# MainMCU.net
KiCad netlist of a schematic drawn in Altium Designer
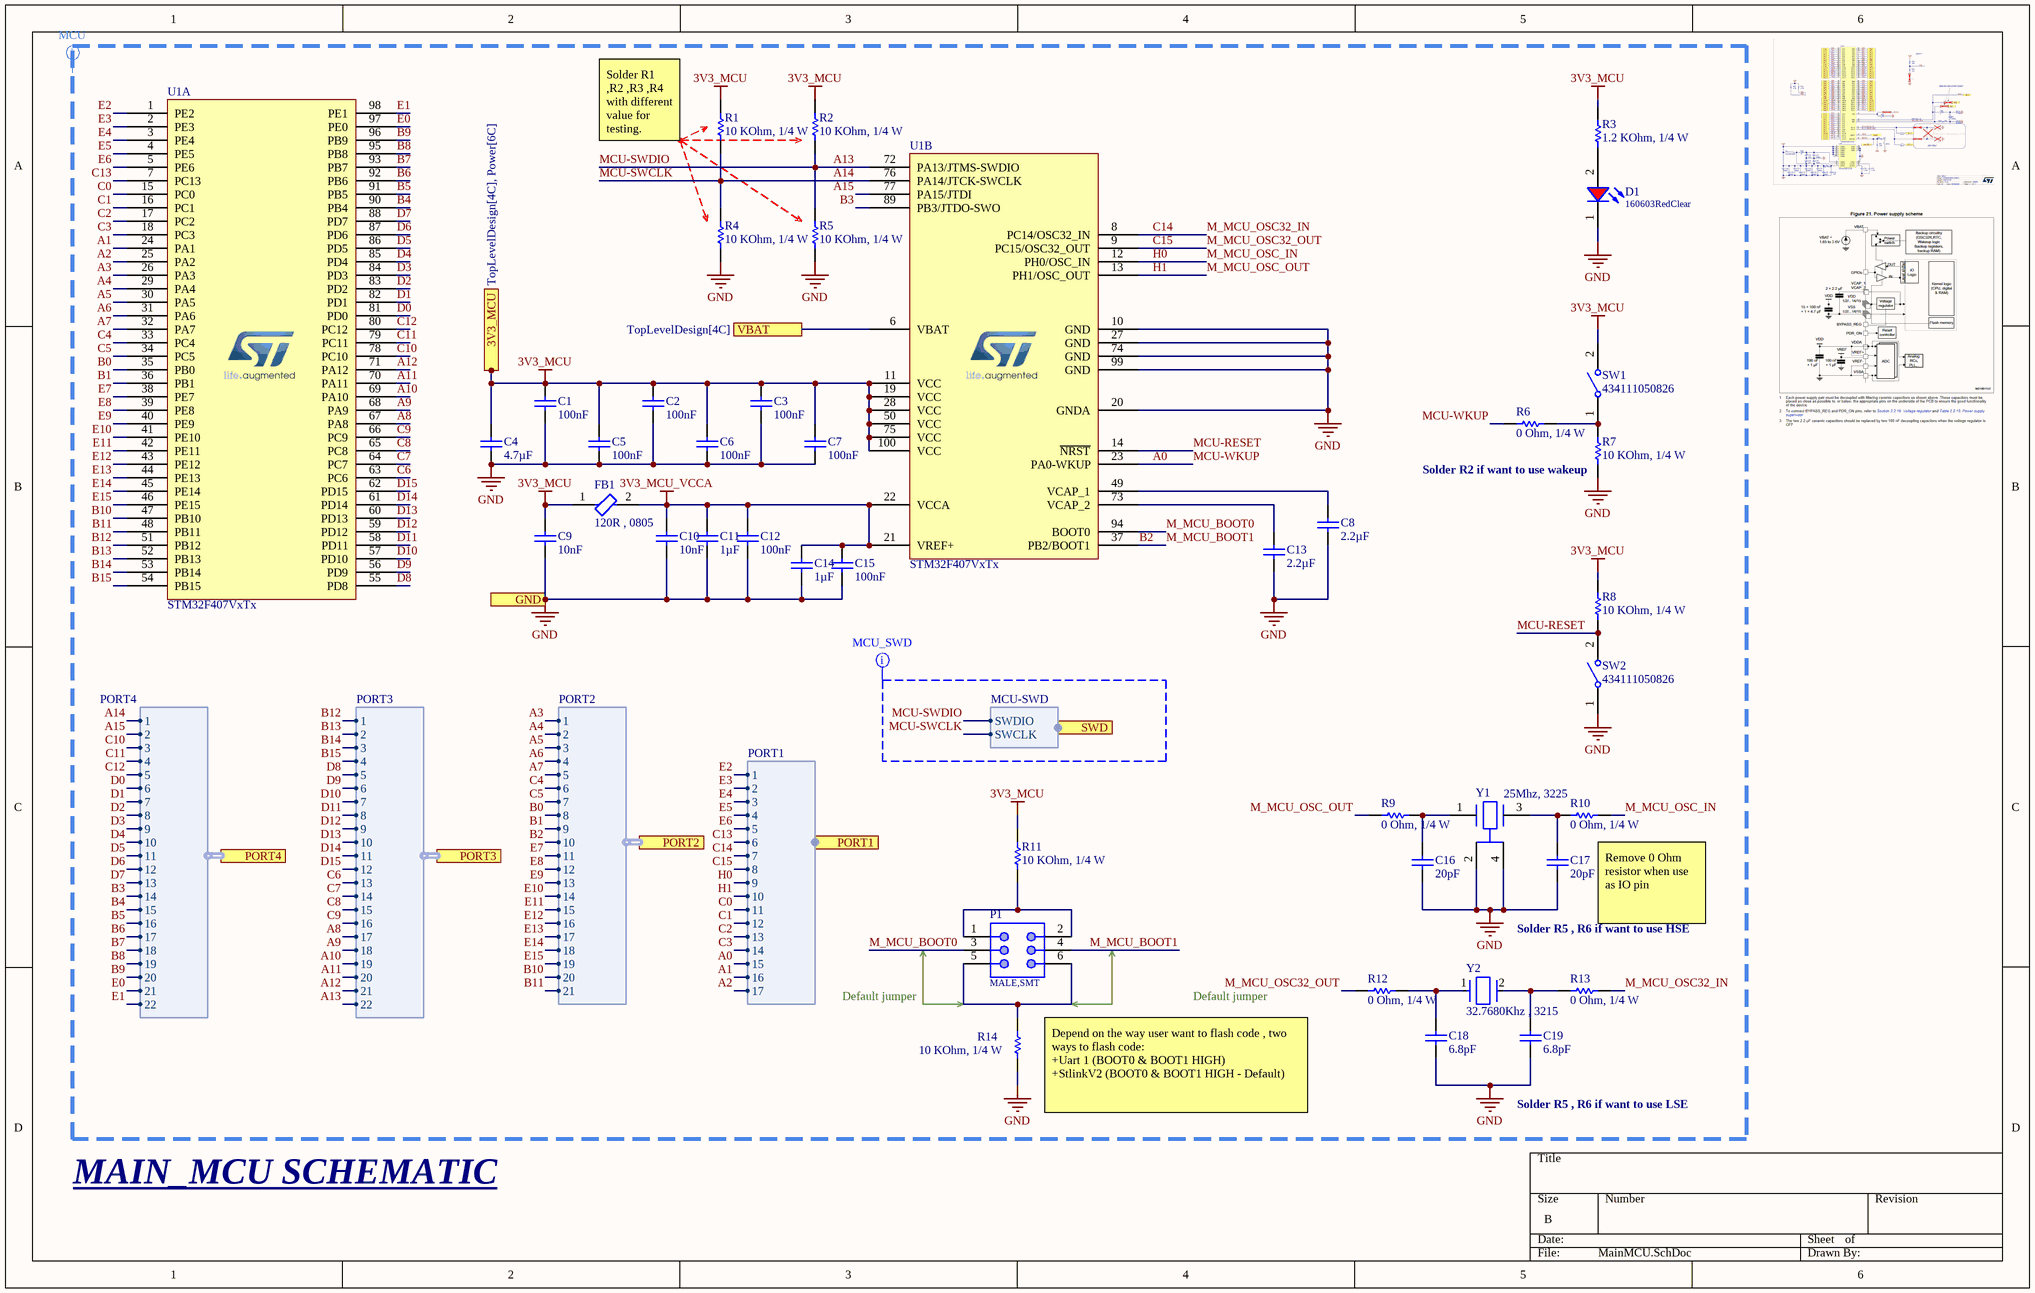
[diagram p0: MainMCU.SchDoc]

(export (version "E")
  (design (tool "Eeschema 10.0.6"))
  (components
    (comp (ref "C1")
      (value "100nF")
      (footprint "CAP_0603")
      (description "CAP, size 0603, 100 nF, 50 VDC")
      (fields
        (field (name "TOLERANCE") "5%")
        (field (name "Comment") "0106031010550")
        (field (name "SOURCE") "Capacitor_0603_5_percent.SchLib")
      )
      (libsource (lib "Tin Tran") (part "0106036820550"))
    )
    (comp (ref "C2")
      (value "100nF")
      (footprint "CAP_0603")
      (description "CAP, size 0603, 100 nF, 50 VDC")
      (fields
        (field (name "TOLERANCE") "5%")
        (field (name "Comment") "0106031010550")
        (field (name "SOURCE") "Capacitor_0603_5_percent.SchLib")
      )
      (libsource (lib "Tin Tran") (part "0106036820550"))
    )
    (comp (ref "C3")
      (value "100nF")
      (footprint "CAP_0603")
      (description "CAP, size 0603, 100 nF, 50 VDC")
      (fields
        (field (name "TOLERANCE") "5%")
        (field (name "Comment") "0106031010550")
        (field (name "SOURCE") "Capacitor_0603_5_percent.SchLib")
      )
      (libsource (lib "Tin Tran") (part "0106036820550"))
    )
    (comp (ref "C4")
      (value "4.7µF")
      (footprint "CAP_0603")
      (description "CAP, size 0603, 4.7 uF, 10 VDC")
      (fields
        (field (name "TOLERANCE") "10%")
        (field (name "Comment") "0106034751010")
        (field (name "SOURCE") "Capacitor_0603_10_percent.SchLib")
      )
      (libsource (lib "Tin Tran") (part "010603475106.3"))
    )
    (comp (ref "C5")
      (value "100nF")
      (footprint "CAP_0603")
      (description "CAP, size 0603, 100 nF, 50 VDC")
      (fields
        (field (name "TOLERANCE") "5%")
        (field (name "Comment") "0106031010550")
        (field (name "SOURCE") "Capacitor_0603_5_percent.SchLib")
      )
      (libsource (lib "Tin Tran") (part "0106036820550"))
    )
    (comp (ref "C6")
      (value "100nF")
      (footprint "CAP_0603")
      (description "CAP, size 0603, 100 nF, 50 VDC")
      (fields
        (field (name "TOLERANCE") "5%")
        (field (name "Comment") "0106031010550")
        (field (name "SOURCE") "Capacitor_0603_5_percent.SchLib")
      )
      (libsource (lib "Tin Tran") (part "0106036820550"))
    )
    (comp (ref "C7")
      (value "100nF")
      (footprint "CAP_0603")
      (description "CAP, size 0603, 100 nF, 50 VDC")
      (fields
        (field (name "TOLERANCE") "5%")
        (field (name "Comment") "0106031010550")
        (field (name "SOURCE") "Capacitor_0603_5_percent.SchLib")
      )
      (libsource (lib "Tin Tran") (part "0106036820550"))
    )
    (comp (ref "C8")
      (value "2.2µF")
      (footprint "CAP_0603")
      (description "CAP, size 0603, 2.2 uF, 10 VDC")
      (fields
        (field (name "TOLERANCE") "10%")
        (field (name "Comment") "0106032251010")
        (field (name "SOURCE") "Capacitor_0603_10_percent.SchLib")
      )
      (libsource (lib "Tin Tran") (part "010603475106.3"))
    )
    (comp (ref "C9")
      (value "10nF")
      (footprint "CAP_0603")
      (description "CAP, size 0603, 10 nF, 50 VDC")
      (fields
        (field (name "TOLERANCE") "5%")
        (field (name "Comment") "0106031030550")
        (field (name "SOURCE") "Capacitor_0603_5_percent.SchLib")
      )
      (libsource (lib "Tin Tran") (part "0106036820550"))
    )
    (comp (ref "C10")
      (value "10nF")
      (footprint "CAP_0603")
      (description "CAP, size 0603, 10 nF, 50 VDC")
      (fields
        (field (name "TOLERANCE") "5%")
        (field (name "Comment") "0106031030550")
        (field (name "SOURCE") "Capacitor_0603_5_percent.SchLib")
      )
      (libsource (lib "Tin Tran") (part "0106036820550"))
    )
    (comp (ref "C11")
      (value "1µF")
      (footprint "CAP_0603")
      (description "CAP, size 0603, 1 uF, 35 VDC")
      (fields
        (field (name "TOLERANCE") "10%")
        (field (name "Comment") "0106031051035")
        (field (name "SOURCE") "Capacitor_0603_10_percent.SchLib")
      )
      (libsource (lib "Tin Tran") (part "010603475106.3"))
    )
    (comp (ref "C12")
      (value "100nF")
      (footprint "CAP_0603")
      (description "CAP, size 0603, 100 nF, 50 VDC")
      (fields
        (field (name "TOLERANCE") "5%")
        (field (name "Comment") "0106031010550")
        (field (name "SOURCE") "Capacitor_0603_5_percent.SchLib")
      )
      (libsource (lib "Tin Tran") (part "0106036820550"))
    )
    (comp (ref "C13")
      (value "2.2µF")
      (footprint "CAP_0603")
      (description "CAP, size 0603, 2.2 uF, 10 VDC")
      (fields
        (field (name "TOLERANCE") "10%")
        (field (name "Comment") "0106032251010")
        (field (name "SOURCE") "Capacitor_0603_10_percent.SchLib")
      )
      (libsource (lib "Tin Tran") (part "010603475106.3"))
    )
    (comp (ref "C14")
      (value "1µF")
      (footprint "CAP_0603")
      (description "CAP, size 0603, 1 uF, 35 VDC")
      (fields
        (field (name "TOLERANCE") "10%")
        (field (name "Comment") "0106031051035")
        (field (name "SOURCE") "Capacitor_0603_10_percent.SchLib")
      )
      (libsource (lib "Tin Tran") (part "010603475106.3"))
    )
    (comp (ref "C15")
      (value "100nF")
      (footprint "CAP_0603")
      (description "CAP, size 0603, 100 nF, 50 VDC")
      (fields
        (field (name "TOLERANCE") "5%")
        (field (name "Comment") "0106031010550")
        (field (name "SOURCE") "Capacitor_0603_5_percent.SchLib")
      )
      (libsource (lib "Tin Tran") (part "0106036820550"))
    )
    (comp (ref "C16")
      (value "20pF")
      (footprint "CAP_0603")
      (description "CAP, size 0603, 20 pF, 50 VDC")
      (fields
        (field (name "TOLERANCE") "5%")
        (field (name "Comment") "0106031000550")
        (field (name "SOURCE") "Capacitor_0603_5_percent.SchLib")
      )
      (libsource (lib "Tin Tran") (part "0106036820550"))
    )
    (comp (ref "C17")
      (value "20pF")
      (footprint "CAP_0603")
      (description "CAP, size 0603, 20 pF, 50 VDC")
      (fields
        (field (name "TOLERANCE") "5%")
        (field (name "Comment") "0106031000550")
        (field (name "SOURCE") "Capacitor_0603_5_percent.SchLib")
      )
      (libsource (lib "Tin Tran") (part "0106036820550"))
    )
    (comp (ref "C18")
      (value "6.8pF")
      (footprint "CAP_0603")
      (description "CAP, size 0603, 6.8 pF, 50 VDC")
      (fields
        (field (name "TOLERANCE") "5%")
        (field (name "Comment") "0106031000550")
        (field (name "SOURCE") "Capacitor_0603_5_percent.SchLib")
      )
      (libsource (lib "Tin Tran") (part "0106036820550"))
    )
    (comp (ref "C19")
      (value "6.8pF")
      (footprint "CAP_0603")
      (description "CAP, size 0603, 6.8 pF, 50 VDC")
      (fields
        (field (name "TOLERANCE") "5%")
        (field (name "Comment") "0106031000550")
        (field (name "SOURCE") "Capacitor_0603_5_percent.SchLib")
      )
      (libsource (lib "Tin Tran") (part "0106036820550"))
    )
    (comp (ref "D1")
      (value "160603RedClear")
      (footprint "WL-SMCW_0603_H=0.7mm")
      (description "WL-SMCW SMT Mono-color Chip LED Waterclear, size 0603, Red, 2V, 140deg")
      (libsource (lib "Tin Tran") (part "160603RedClear"))
    )
    (comp (ref "FB1")
      (value "120R , 0805")
      (footprint "FP-BLM18-0_15-t0_8-MFG")
      (description "Ferrite Chip, 1 Function(s), 2A, 2 Pin(s)")
      (libsource (lib "Tin Tran") (part "5f30dd21d616792df468990f7003faa"))
    )
    (comp (ref "P1")
      (value "MALE,SMT")
      (footprint "61030621121")
      (description "WR-PHD Pin Header, SMT, pitch 2.54mm, Dual Row, Vertical, 6p")
      (fields
        (field (name "MANUFACTURER") "Wurth Elektronik")
        (field (name "MANUFACTURER PART NUMBER") "61030621121")
      )
      (libsource (lib "Tin Tran") (part "61300621121"))
    )
    (comp (ref "R1")
      (value "10 KOhm, 1/4 W")
      (footprint "resistor_0603")
      (description "RES, size 0603, 10 KOhm, 1/4 W")
      (fields (field (name "Comment") "0006031031"))
      (libsource (lib "Tin Tran") (part "00060371541"))
    )
    (comp (ref "R2")
      (value "10 KOhm, 1/4 W")
      (footprint "resistor_0603")
      (description "RES, size 0603, 10 KOhm, 1/4 W")
      (fields (field (name "Comment") "0006031031"))
      (libsource (lib "Tin Tran") (part "00060371541"))
    )
    (comp (ref "R3")
      (value "1.2 KOhm, 1/4 W")
      (footprint "resistor_0603")
      (description "RES, size 0603, 1.2 KOhm, 1/4 W")
      (fields (field (name "Comment") "0006031221"))
      (libsource (lib "Tin Tran") (part "00060371541"))
    )
    (comp (ref "R4")
      (value "10 KOhm, 1/4 W")
      (footprint "resistor_0603")
      (description "RES, size 0603, 10 KOhm, 1/4 W")
      (fields (field (name "Comment") "0006031031"))
      (libsource (lib "Tin Tran") (part "00060371541"))
    )
    (comp (ref "R5")
      (value "10 KOhm, 1/4 W")
      (footprint "resistor_0603")
      (description "RES, size 0603, 10 KOhm, 1/4 W")
      (fields (field (name "Comment") "0006031031"))
      (libsource (lib "Tin Tran") (part "00060371541"))
    )
    (comp (ref "R6")
      (value "0 Ohm, 1/4 W")
      (footprint "resistor_0603")
      (description "RES, size 0603, 0 Ohm, 1/4 W")
      (fields (field (name "Comment") "0006030001"))
      (libsource (lib "Tin Tran") (part "00060371541"))
    )
    (comp (ref "R7")
      (value "10 KOhm, 1/4 W")
      (footprint "resistor_0603")
      (description "RES, size 0603, 10 KOhm, 1/4 W")
      (fields (field (name "Comment") "0006031031"))
      (libsource (lib "Tin Tran") (part "00060371541"))
    )
    (comp (ref "R8")
      (value "10 KOhm, 1/4 W")
      (footprint "resistor_0603")
      (description "RES, size 0603, 10 KOhm, 1/4 W")
      (fields (field (name "Comment") "0006031031"))
      (libsource (lib "Tin Tran") (part "00060371541"))
    )
    (comp (ref "R9")
      (value "0 Ohm, 1/4 W")
      (footprint "resistor_0603")
      (description "RES, size 0603, 0 Ohm, 1/4 W")
      (fields (field (name "Comment") "0006030001"))
      (libsource (lib "Tin Tran") (part "00060371541"))
    )
    (comp (ref "R10")
      (value "0 Ohm, 1/4 W")
      (footprint "resistor_0603")
      (description "RES, size 0603, 0 Ohm, 1/4 W")
      (fields (field (name "Comment") "0006030001"))
      (libsource (lib "Tin Tran") (part "00060371541"))
    )
    (comp (ref "R11")
      (value "10 KOhm, 1/4 W")
      (footprint "resistor_0603")
      (description "RES, size 0603, 10 KOhm, 1/4 W")
      (fields (field (name "Comment") "0006031031"))
      (libsource (lib "Tin Tran") (part "00060371541"))
    )
    (comp (ref "R12")
      (value "0 Ohm, 1/4 W")
      (footprint "resistor_0603")
      (description "RES, size 0603, 0 Ohm, 1/4 W")
      (fields (field (name "Comment") "0006030001"))
      (libsource (lib "Tin Tran") (part "00060371541"))
    )
    (comp (ref "R13")
      (value "0 Ohm, 1/4 W")
      (footprint "resistor_0603")
      (description "RES, size 0603, 0 Ohm, 1/4 W")
      (fields (field (name "Comment") "0006030001"))
      (libsource (lib "Tin Tran") (part "00060371541"))
    )
    (comp (ref "R14")
      (value "10 KOhm, 1/4 W")
      (footprint "resistor_0603")
      (description "RES, size 0603, 10 KOhm, 1/4 W")
      (fields (field (name "Comment") "0006031031"))
      (libsource (lib "Tin Tran") (part "00060371541"))
    )
    (comp (ref "SW1")
      (value "434111050826")
      (footprint "WS-TASV_L6W3.5H5_4341x10508x6")
      (description "WS-TASV SMT Tact Switch, L6 x W3.5 x H5mm, 260g, SPST-NO, 12V, 50mA")
      (fields (field (name "MANUFACTURER") "Wurth Elektronik"))
      (libsource (lib "Tin Tran") (part "434111050826"))
    )
    (comp (ref "SW2")
      (value "434111050826")
      (footprint "WS-TASV_L6W3.5H5_4341x10508x6")
      (description "WS-TASV SMT Tact Switch, L6 x W3.5 x H5mm, 260g, SPST-NO, 12V, 50mA")
      (fields (field (name "MANUFACTURER") "Wurth Elektronik"))
      (libsource (lib "Tin Tran") (part "434111050826"))
    )
    (comp (ref "U1")
      (value "STM32F407VxTx")
      (footprint "STM32F407VGTx")
      (description "ARM Microcontrollers - MCU ARM M4 1024 FLASH 168 Mhz 192kB SRAM")
      (fields (field (name "PART NUMBER") "STM32F407IGTx") (field (name "MANUFACTURER") "STM"))
      (libsource (lib "Tin Tran") (part "STM32F407VGTx"))
    )
    (comp (ref "Y1")
      (value "25Mhz, 3225")
      (footprint "FP-NX3225SA-MFG")
      (description "CRYSTAL 25.0000MHZ 8PF SMD")
      (fields
        (field (name "OCTOPART") "https://octopart.com/nx3225sa-25.000m-std-crs-2-ndk-51374293")
        (field (name "TOLERANCE") "15ppm")
      )
      (libsource (lib "Tin Tran") (part "CMP-200220-000002-1"))
    )
    (comp (ref "Y2")
      (value "32.7680Khz , 3215")
      (footprint "FP-FC-135-MFG")
      (description "Parallel - Fundamental Quartz Crystal, 0.032768MHz Nom")
      (libsource (lib "Tin Tran") (part "c23a69dc6c9e2f18f2079038eb95dd1"))
    )
  )
  (nets
    (net (code "6") (name "/A0") (class "Default")
      (node (ref "R6") (pin "1") (pinfunction "1_1") (pintype "passive"))
      (node (ref "U1") (pin "23") (pinfunction "PA0-WKUP_23") (pintype "passive"))
    )
    (net (code "7") (name "/A1") (class "Default")
      (node (ref "U1") (pin "24") (pinfunction "PA1_24") (pintype "passive"))
    )
    (net (code "8") (name "/A2") (class "Default")
      (node (ref "U1") (pin "25") (pinfunction "PA2_25") (pintype "passive"))
    )
    (net (code "9") (name "/A3") (class "Default")
      (node (ref "U1") (pin "26") (pinfunction "PA3_26") (pintype "passive"))
    )
    (net (code "10") (name "/A4") (class "Default")
      (node (ref "U1") (pin "29") (pinfunction "PA4_29") (pintype "passive"))
    )
    (net (code "11") (name "/A5") (class "Default")
      (node (ref "U1") (pin "30") (pinfunction "PA5_30") (pintype "passive"))
    )
    (net (code "12") (name "/A6") (class "Default")
      (node (ref "U1") (pin "31") (pinfunction "PA6_31") (pintype "passive"))
    )
    (net (code "13") (name "/A7") (class "Default")
      (node (ref "U1") (pin "32") (pinfunction "PA7_32") (pintype "passive"))
    )
    (net (code "14") (name "/A8") (class "Default")
      (node (ref "U1") (pin "67") (pinfunction "PA8_67") (pintype "passive"))
    )
    (net (code "15") (name "/A9") (class "Default")
      (node (ref "U1") (pin "68") (pinfunction "PA9_68") (pintype "passive"))
    )
    (net (code "16") (name "/A10") (class "Default")
      (node (ref "U1") (pin "69") (pinfunction "PA10_69") (pintype "passive"))
    )
    (net (code "17") (name "/A11") (class "Default")
      (node (ref "U1") (pin "70") (pinfunction "PA11_70") (pintype "passive"))
    )
    (net (code "18") (name "/A12") (class "Default")
      (node (ref "U1") (pin "71") (pinfunction "PA12_71") (pintype "passive"))
    )
    (net (code "19") (name "/A13") (class "Default")
      (node (ref "R2") (pin "1") (pinfunction "1_1") (pintype "passive"))
      (node (ref "R5") (pin "2") (pinfunction "2_2") (pintype "passive"))
      (node (ref "U1") (pin "72") (pinfunction "PA13/JTMS-SWDIO_72") (pintype "passive"))
    )
    (net (code "20") (name "/A14") (class "Default")
      (node (ref "R1") (pin "1") (pinfunction "1_1") (pintype "passive"))
      (node (ref "R4") (pin "2") (pinfunction "2_2") (pintype "passive"))
      (node (ref "U1") (pin "76") (pinfunction "PA14/JTCK-SWCLK_76") (pintype "passive"))
    )
    (net (code "21") (name "/A15") (class "Default")
      (node (ref "U1") (pin "77") (pinfunction "PA15/JTDI_77") (pintype "passive"))
    )
    (net (code "22") (name "/B0") (class "Default")
      (node (ref "U1") (pin "35") (pinfunction "PB0_35") (pintype "passive"))
    )
    (net (code "23") (name "/B1") (class "Default")
      (node (ref "U1") (pin "36") (pinfunction "PB1_36") (pintype "passive"))
    )
    (net (code "24") (name "/B2") (class "Default")
      (node (ref "P1") (pin "4") (pinfunction "4_4") (pintype "passive"))
      (node (ref "U1") (pin "37") (pinfunction "PB2/BOOT1_37") (pintype "passive"))
    )
    (net (code "25") (name "/B3") (class "Default")
      (node (ref "U1") (pin "89") (pinfunction "PB3/JTDO-SWO_89") (pintype "passive"))
    )
    (net (code "26") (name "/B4") (class "Default")
      (node (ref "U1") (pin "90") (pinfunction "PB4_90") (pintype "passive"))
    )
    (net (code "27") (name "/B5") (class "Default")
      (node (ref "U1") (pin "91") (pinfunction "PB5_91") (pintype "passive"))
    )
    (net (code "28") (name "/B6") (class "Default")
      (node (ref "U1") (pin "92") (pinfunction "PB6_92") (pintype "passive"))
    )
    (net (code "29") (name "/B7") (class "Default")
      (node (ref "U1") (pin "93") (pinfunction "PB7_93") (pintype "passive"))
    )
    (net (code "30") (name "/B8") (class "Default")
      (node (ref "U1") (pin "95") (pinfunction "PB8_95") (pintype "passive"))
    )
    (net (code "31") (name "/B9") (class "Default")
      (node (ref "U1") (pin "96") (pinfunction "PB9_96") (pintype "passive"))
    )
    (net (code "32") (name "/B10") (class "Default")
      (node (ref "U1") (pin "47") (pinfunction "PB10_47") (pintype "passive"))
    )
    (net (code "33") (name "/B11") (class "Default")
      (node (ref "U1") (pin "48") (pinfunction "PB11_48") (pintype "passive"))
    )
    (net (code "34") (name "/B12") (class "Default")
      (node (ref "U1") (pin "51") (pinfunction "PB12_51") (pintype "passive"))
    )
    (net (code "35") (name "/B13") (class "Default")
      (node (ref "U1") (pin "52") (pinfunction "PB13_52") (pintype "passive"))
    )
    (net (code "36") (name "/B14") (class "Default")
      (node (ref "U1") (pin "53") (pinfunction "PB14_53") (pintype "passive"))
    )
    (net (code "37") (name "/B15") (class "Default")
      (node (ref "U1") (pin "54") (pinfunction "PB15_54") (pintype "passive"))
    )
    (net (code "38") (name "/C0") (class "Default")
      (node (ref "U1") (pin "15") (pinfunction "PC0_15") (pintype "passive"))
    )
    (net (code "39") (name "/C1") (class "Default")
      (node (ref "U1") (pin "16") (pinfunction "PC1_16") (pintype "passive"))
    )
    (net (code "40") (name "/C2") (class "Default")
      (node (ref "U1") (pin "17") (pinfunction "PC2_17") (pintype "passive"))
    )
    (net (code "41") (name "/C3") (class "Default")
      (node (ref "U1") (pin "18") (pinfunction "PC3_18") (pintype "passive"))
    )
    (net (code "42") (name "/C4") (class "Default")
      (node (ref "U1") (pin "33") (pinfunction "PC4_33") (pintype "passive"))
    )
    (net (code "43") (name "/C5") (class "Default")
      (node (ref "U1") (pin "34") (pinfunction "PC5_34") (pintype "passive"))
    )
    (net (code "44") (name "/C6") (class "Default")
      (node (ref "U1") (pin "63") (pinfunction "PC6_63") (pintype "passive"))
    )
    (net (code "45") (name "/C7") (class "Default")
      (node (ref "U1") (pin "64") (pinfunction "PC7_64") (pintype "passive"))
    )
    (net (code "46") (name "/C8") (class "Default")
      (node (ref "U1") (pin "65") (pinfunction "PC8_65") (pintype "passive"))
    )
    (net (code "47") (name "/C9") (class "Default")
      (node (ref "U1") (pin "66") (pinfunction "PC9_66") (pintype "passive"))
    )
    (net (code "48") (name "/C10") (class "Default")
      (node (ref "U1") (pin "78") (pinfunction "PC10_78") (pintype "passive"))
    )
    (net (code "49") (name "/C11") (class "Default")
      (node (ref "U1") (pin "79") (pinfunction "PC11_79") (pintype "passive"))
    )
    (net (code "50") (name "/C12") (class "Default")
      (node (ref "U1") (pin "80") (pinfunction "PC12_80") (pintype "passive"))
    )
    (net (code "51") (name "/C13") (class "Default")
      (node (ref "U1") (pin "7") (pinfunction "PC13_7") (pintype "passive"))
    )
    (net (code "52") (name "/C14") (class "Default")
      (node (ref "R13") (pin "2") (pinfunction "2_2") (pintype "passive"))
      (node (ref "U1") (pin "8") (pinfunction "PC14/OSC32_IN_8") (pintype "passive"))
    )
    (net (code "53") (name "/C15") (class "Default")
      (node (ref "R12") (pin "1") (pinfunction "1_1") (pintype "passive"))
      (node (ref "U1") (pin "9") (pinfunction "PC15/OSC32_OUT_9") (pintype "passive"))
    )
    (net (code "54") (name "/D0") (class "Default")
      (node (ref "U1") (pin "81") (pinfunction "PD0_81") (pintype "passive"))
    )
    (net (code "55") (name "/D1") (class "Default")
      (node (ref "U1") (pin "82") (pinfunction "PD1_82") (pintype "passive"))
    )
    (net (code "56") (name "/D2") (class "Default")
      (node (ref "U1") (pin "83") (pinfunction "PD2_83") (pintype "passive"))
    )
    (net (code "57") (name "/D3") (class "Default")
      (node (ref "U1") (pin "84") (pinfunction "PD3_84") (pintype "passive"))
    )
    (net (code "58") (name "/D4") (class "Default")
      (node (ref "U1") (pin "85") (pinfunction "PD4_85") (pintype "passive"))
    )
    (net (code "59") (name "/D5") (class "Default")
      (node (ref "U1") (pin "86") (pinfunction "PD5_86") (pintype "passive"))
    )
    (net (code "60") (name "/D6") (class "Default")
      (node (ref "U1") (pin "87") (pinfunction "PD6_87") (pintype "passive"))
    )
    (net (code "61") (name "/D7") (class "Default")
      (node (ref "U1") (pin "88") (pinfunction "PD7_88") (pintype "passive"))
    )
    (net (code "62") (name "/D8") (class "Default")
      (node (ref "U1") (pin "55") (pinfunction "PD8_55") (pintype "passive"))
    )
    (net (code "63") (name "/D9") (class "Default")
      (node (ref "U1") (pin "56") (pinfunction "PD9_56") (pintype "passive"))
    )
    (net (code "64") (name "/D10") (class "Default")
      (node (ref "U1") (pin "57") (pinfunction "PD10_57") (pintype "passive"))
    )
    (net (code "65") (name "/D11") (class "Default")
      (node (ref "U1") (pin "58") (pinfunction "PD11_58") (pintype "passive"))
    )
    (net (code "66") (name "/D12") (class "Default")
      (node (ref "U1") (pin "59") (pinfunction "PD12_59") (pintype "passive"))
    )
    (net (code "67") (name "/D13") (class "Default")
      (node (ref "U1") (pin "60") (pinfunction "PD13_60") (pintype "passive"))
    )
    (net (code "68") (name "/D14") (class "Default")
      (node (ref "U1") (pin "61") (pinfunction "PD14_61") (pintype "passive"))
    )
    (net (code "69") (name "/D15") (class "Default")
      (node (ref "U1") (pin "62") (pinfunction "PD15_62") (pintype "passive"))
    )
    (net (code "70") (name "/E0") (class "Default")
      (node (ref "U1") (pin "97") (pinfunction "PE0_97") (pintype "passive"))
    )
    (net (code "71") (name "/E1") (class "Default")
      (node (ref "U1") (pin "98") (pinfunction "PE1_98") (pintype "passive"))
    )
    (net (code "72") (name "/E2") (class "Default")
      (node (ref "U1") (pin "1") (pinfunction "PE2_1") (pintype "passive"))
    )
    (net (code "73") (name "/E3") (class "Default")
      (node (ref "U1") (pin "2") (pinfunction "PE3_2") (pintype "passive"))
    )
    (net (code "74") (name "/E4") (class "Default")
      (node (ref "U1") (pin "3") (pinfunction "PE4_3") (pintype "passive"))
    )
    (net (code "75") (name "/E5") (class "Default")
      (node (ref "U1") (pin "4") (pinfunction "PE5_4") (pintype "passive"))
    )
    (net (code "76") (name "/E6") (class "Default")
      (node (ref "U1") (pin "5") (pinfunction "PE6_5") (pintype "passive"))
    )
    (net (code "77") (name "/E7") (class "Default")
      (node (ref "U1") (pin "38") (pinfunction "PE7_38") (pintype "passive"))
    )
    (net (code "78") (name "/E8") (class "Default")
      (node (ref "U1") (pin "39") (pinfunction "PE8_39") (pintype "passive"))
    )
    (net (code "79") (name "/E9") (class "Default")
      (node (ref "U1") (pin "40") (pinfunction "PE9_40") (pintype "passive"))
    )
    (net (code "80") (name "/E10") (class "Default")
      (node (ref "U1") (pin "41") (pinfunction "PE10_41") (pintype "passive"))
    )
    (net (code "81") (name "/E11") (class "Default")
      (node (ref "U1") (pin "42") (pinfunction "PE11_42") (pintype "passive"))
    )
    (net (code "82") (name "/E12") (class "Default")
      (node (ref "U1") (pin "43") (pinfunction "PE12_43") (pintype "passive"))
    )
    (net (code "83") (name "/E13") (class "Default")
      (node (ref "U1") (pin "44") (pinfunction "PE13_44") (pintype "passive"))
    )
    (net (code "84") (name "/E14") (class "Default")
      (node (ref "U1") (pin "45") (pinfunction "PE14_45") (pintype "passive"))
    )
    (net (code "85") (name "/E15") (class "Default")
      (node (ref "U1") (pin "46") (pinfunction "PE15_46") (pintype "passive"))
    )
    (net (code "86") (name "/H0") (class "Default")
      (node (ref "R10") (pin "2") (pinfunction "2_2") (pintype "passive"))
      (node (ref "U1") (pin "12") (pinfunction "PH0/OSC_IN_12") (pintype "passive"))
    )
    (net (code "87") (name "/H1") (class "Default")
      (node (ref "R9") (pin "1") (pinfunction "1_1") (pintype "passive"))
      (node (ref "U1") (pin "13") (pinfunction "PH1/OSC_OUT_13") (pintype "passive"))
    )
    (net (code "88") (name "/MCU-RESET") (class "Default")
      (node (ref "R8") (pin "1") (pinfunction "1_1") (pintype "passive"))
      (node (ref "SW2") (pin "2") (pinfunction "2_2") (pintype "passive"))
      (node (ref "U1") (pin "14") (pinfunction "~{NRST}_14") (pintype "passive"))
    )
    (net (code "89") (name "/M_MCU_BOOT0") (class "Default")
      (node (ref "P1") (pin "3") (pinfunction "3_3") (pintype "passive"))
      (node (ref "U1") (pin "94") (pinfunction "BOOT0_94") (pintype "passive"))
    )
    (net (code "90") (name "/VBAT") (class "Default")
      (node (ref "U1") (pin "6") (pinfunction "VBAT_6") (pintype "passive"))
    )
    (net (code "96") (name "3V3_MCU") (class "Default")
      (node (ref "C1") (pin "2") (pinfunction "2_2") (pintype "passive"))
      (node (ref "C2") (pin "2") (pinfunction "2_2") (pintype "passive"))
      (node (ref "C3") (pin "2") (pinfunction "2_2") (pintype "passive"))
      (node (ref "C4") (pin "2") (pinfunction "2_2") (pintype "passive"))
      (node (ref "C5") (pin "2") (pinfunction "2_2") (pintype "passive"))
      (node (ref "C6") (pin "2") (pinfunction "2_2") (pintype "passive"))
      (node (ref "C7") (pin "2") (pinfunction "2_2") (pintype "passive"))
      (node (ref "C9") (pin "2") (pinfunction "2_2") (pintype "passive"))
      (node (ref "FB1") (pin "1") (pinfunction "1_1") (pintype "passive"))
      (node (ref "R1") (pin "2") (pinfunction "2_2") (pintype "passive"))
      (node (ref "R11") (pin "2") (pinfunction "2_2") (pintype "passive"))
      (node (ref "R2") (pin "2") (pinfunction "2_2") (pintype "passive"))
      (node (ref "R3") (pin "2") (pinfunction "2_2") (pintype "passive"))
      (node (ref "R8") (pin "2") (pinfunction "2_2") (pintype "passive"))
      (node (ref "SW1") (pin "2") (pinfunction "2_2") (pintype "passive"))
      (node (ref "U1") (pin "100") (pinfunction "VCC_100") (pintype "passive"))
      (node (ref "U1") (pin "11") (pinfunction "VCC_11") (pintype "passive"))
      (node (ref "U1") (pin "19") (pinfunction "VCC_19") (pintype "passive"))
      (node (ref "U1") (pin "28") (pinfunction "VCC_28") (pintype "passive"))
      (node (ref "U1") (pin "50") (pinfunction "VCC_50") (pintype "passive"))
      (node (ref "U1") (pin "75") (pinfunction "VCC_75") (pintype "passive"))
    )
    (net (code "97") (name "3V3_MCU_VCCA") (class "Default")
      (node (ref "C10") (pin "2") (pinfunction "2_2") (pintype "passive"))
      (node (ref "C11") (pin "2") (pinfunction "2_2") (pintype "passive"))
      (node (ref "C12") (pin "2") (pinfunction "2_2") (pintype "passive"))
      (node (ref "C14") (pin "2") (pinfunction "2_2") (pintype "passive"))
      (node (ref "C15") (pin "2") (pinfunction "2_2") (pintype "passive"))
      (node (ref "FB1") (pin "2") (pinfunction "2_2") (pintype "passive"))
      (node (ref "U1") (pin "21") (pinfunction "VREF+_21") (pintype "passive"))
      (node (ref "U1") (pin "22") (pinfunction "VCCA_22") (pintype "passive"))
    )
    (net (code "98") (name "GND") (class "Default")
      (node (ref "C1") (pin "1") (pinfunction "1_1") (pintype "passive"))
      (node (ref "C10") (pin "1") (pinfunction "1_1") (pintype "passive"))
      (node (ref "C11") (pin "1") (pinfunction "1_1") (pintype "passive"))
      (node (ref "C12") (pin "1") (pinfunction "1_1") (pintype "passive"))
      (node (ref "C13") (pin "1") (pinfunction "1_1") (pintype "passive"))
      (node (ref "C14") (pin "1") (pinfunction "1_1") (pintype "passive"))
      (node (ref "C15") (pin "1") (pinfunction "1_1") (pintype "passive"))
      (node (ref "C16") (pin "1") (pinfunction "1_1") (pintype "passive"))
      (node (ref "C17") (pin "1") (pinfunction "1_1") (pintype "passive"))
      (node (ref "C18") (pin "1") (pinfunction "1_1") (pintype "passive"))
      (node (ref "C19") (pin "1") (pinfunction "1_1") (pintype "passive"))
      (node (ref "C2") (pin "1") (pinfunction "1_1") (pintype "passive"))
      (node (ref "C3") (pin "1") (pinfunction "1_1") (pintype "passive"))
      (node (ref "C4") (pin "1") (pinfunction "1_1") (pintype "passive"))
      (node (ref "C5") (pin "1") (pinfunction "1_1") (pintype "passive"))
      (node (ref "C6") (pin "1") (pinfunction "1_1") (pintype "passive"))
      (node (ref "C7") (pin "1") (pinfunction "1_1") (pintype "passive"))
      (node (ref "C8") (pin "1") (pinfunction "1_1") (pintype "passive"))
      (node (ref "C9") (pin "1") (pinfunction "1_1") (pintype "passive"))
      (node (ref "D1") (pin "1") (pinfunction "K_1") (pintype "passive"))
      (node (ref "R14") (pin "1") (pinfunction "1_1") (pintype "passive"))
      (node (ref "R4") (pin "1") (pinfunction "1_1") (pintype "passive"))
      (node (ref "R5") (pin "1") (pinfunction "1_1") (pintype "passive"))
      (node (ref "R7") (pin "1") (pinfunction "1_1") (pintype "passive"))
      (node (ref "SW2") (pin "1") (pinfunction "1_1") (pintype "passive"))
      (node (ref "U1") (pin "10") (pinfunction "GND_10") (pintype "passive"))
      (node (ref "U1") (pin "20") (pinfunction "GNDA_20") (pintype "passive"))
      (node (ref "U1") (pin "27") (pinfunction "GND_27") (pintype "passive"))
      (node (ref "U1") (pin "74") (pinfunction "GND_74") (pintype "passive"))
      (node (ref "U1") (pin "99") (pinfunction "GND_99") (pintype "passive"))
      (node (ref "Y1") (pin "2") (pinfunction "GND_2") (pintype "power_in"))
      (node (ref "Y1") (pin "4") (pinfunction "GND_4") (pintype "power_in"))
    )
    (net (code "99") (name "Net-(C16-Pad2)") (class "Default")
      (node (ref "C16") (pin "2") (pinfunction "2_2") (pintype "passive"))
      (node (ref "R9") (pin "2") (pinfunction "2_2") (pintype "passive"))
      (node (ref "Y1") (pin "1") (pinfunction "1_1") (pintype "passive"))
    )
    (net (code "100") (name "Net-(C17-Pad2)") (class "Default")
      (node (ref "C17") (pin "2") (pinfunction "2_2") (pintype "passive"))
      (node (ref "R10") (pin "1") (pinfunction "1_1") (pintype "passive"))
      (node (ref "Y1") (pin "3") (pinfunction "3_3") (pintype "passive"))
    )
    (net (code "101") (name "Net-(C18-Pad2)") (class "Default")
      (node (ref "C18") (pin "2") (pinfunction "2_2") (pintype "passive"))
      (node (ref "R12") (pin "2") (pinfunction "2_2") (pintype "passive"))
      (node (ref "Y2") (pin "1") (pinfunction "1_1") (pintype "passive"))
    )
    (net (code "102") (name "Net-(C19-Pad2)") (class "Default")
      (node (ref "C19") (pin "2") (pinfunction "2_2") (pintype "passive"))
      (node (ref "R13") (pin "1") (pinfunction "1_1") (pintype "passive"))
      (node (ref "Y2") (pin "2") (pinfunction "2_2") (pintype "passive"))
    )
    (net (code "103") (name "Net-(D1-A)") (class "Default")
      (node (ref "D1") (pin "2") (pinfunction "A_2") (pintype "passive"))
      (node (ref "R3") (pin "1") (pinfunction "1_1") (pintype "passive"))
    )
    (net (code "104") (name "Net-(P1-Pad1)") (class "Default")
      (node (ref "P1") (pin "1") (pinfunction "1_1") (pintype "passive"))
      (node (ref "P1") (pin "2") (pinfunction "2_2") (pintype "passive"))
      (node (ref "R11") (pin "1") (pinfunction "1_1") (pintype "passive"))
    )
    (net (code "105") (name "Net-(P1-Pad5)") (class "Default")
      (node (ref "P1") (pin "5") (pinfunction "5_5") (pintype "passive"))
      (node (ref "P1") (pin "6") (pinfunction "6_6") (pintype "passive"))
      (node (ref "R14") (pin "2") (pinfunction "2_2") (pintype "passive"))
    )
    (net (code "106") (name "Net-(R6-Pad2)") (class "Default")
      (node (ref "R6") (pin "2") (pinfunction "2_2") (pintype "passive"))
      (node (ref "R7") (pin "2") (pinfunction "2_2") (pintype "passive"))
      (node (ref "SW1") (pin "1") (pinfunction "1_1") (pintype "passive"))
    )
    (net (code "107") (name "Net-(U1B-VCAP_1)") (class "Default")
      (node (ref "C8") (pin "2") (pinfunction "2_2") (pintype "passive"))
      (node (ref "U1") (pin "49") (pinfunction "VCAP_1_49") (pintype "passive"))
    )
    (net (code "108") (name "Net-(U1B-VCAP_2)") (class "Default")
      (node (ref "C13") (pin "2") (pinfunction "2_2") (pintype "passive"))
      (node (ref "U1") (pin "73") (pinfunction "VCAP_2_73") (pintype "passive"))
    )
  )
)
